# UV_BOX.net
KiCad netlist of a schematic drawn in EAGLE
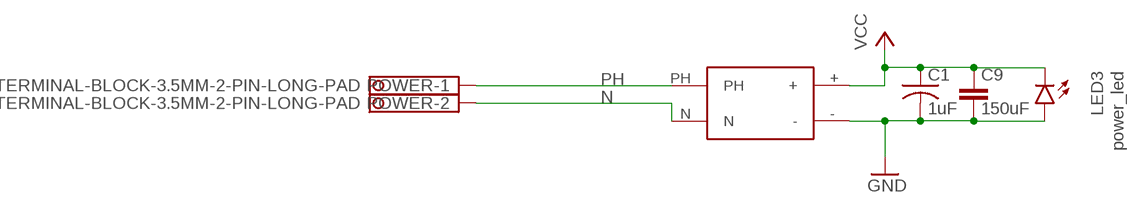
[diagram p0: schematic, sheet 1]
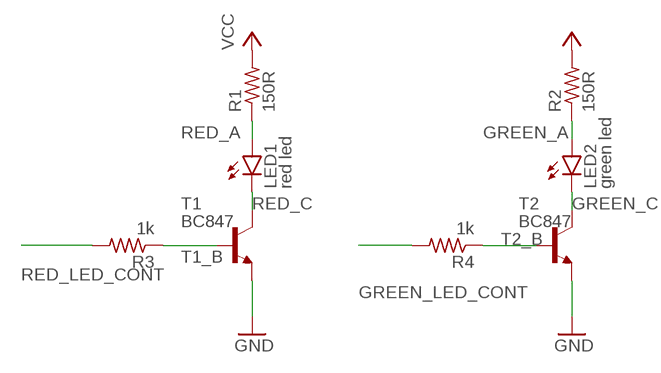
[diagram p1: schematic, sheet 2]
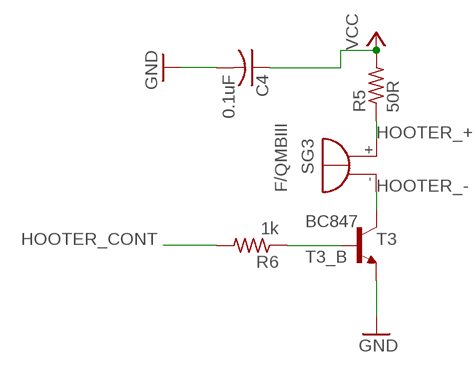
[diagram p2: schematic, sheet 3]
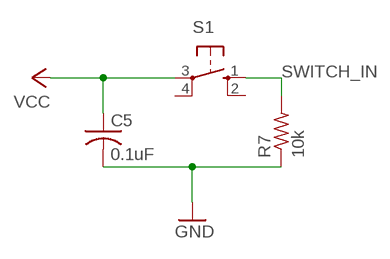
[diagram p3: schematic, sheet 4]
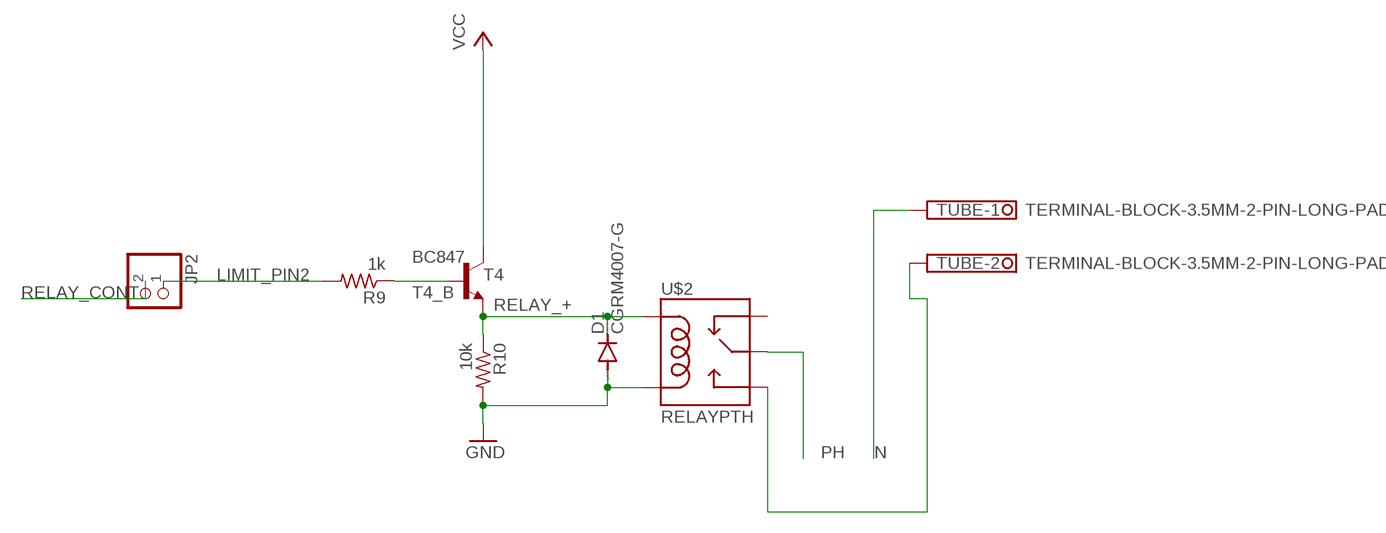
[diagram p4: schematic, sheet 5]
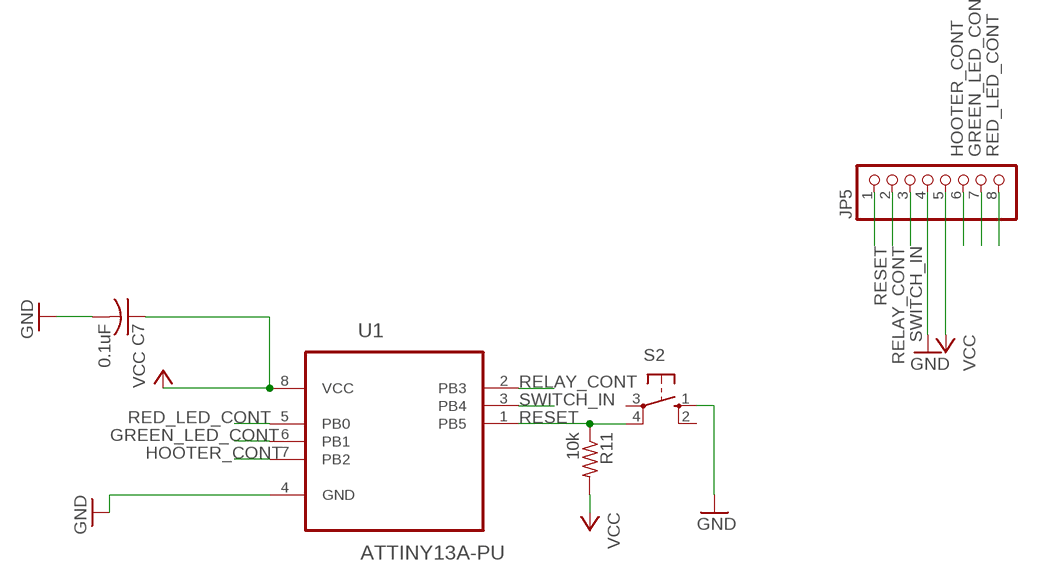
[diagram p5: schematic, sheet 6]

(export (version "E")
  (design (tool "Eeschema 10.0.6"))
  (components
    (comp (ref "D1")
      (value "CGRM4007-G")
      (footprint "eagle-import:SOD-123_MINI-SMA")
      (libsource (lib "eagle-import") (part "CGRM400-G7"))
    )
    (comp (ref "JP2")
      (value "PINHD-1X2")
      (footprint "eagle-import:1X02")
      (libsource (lib "eagle-import") (part "PINHD-1X2"))
    )
    (comp (ref "R9")
      (value "1k")
      (footprint "eagle-import:R1206")
      (libsource (lib "eagle-import") (part "R-US_R1206"))
    )
    (comp (ref "R10")
      (value "10k")
      (footprint "eagle-import:R1206")
      (libsource (lib "eagle-import") (part "R-US_R1206"))
    )
    (comp (ref "T4")
      (value "BC847")
      (footprint "eagle-import:SOT23")
      (libsource (lib "eagle-import") (part "BC847"))
    )
    (comp (ref "TUBE")
      (value "TERMINAL-BLOCK-3.5MM-2-PIN-LONG-PAD")
      (footprint "eagle-import:TERMINAL-BLOCK-2-PIN-3.5MM-LONG-PAD")
      (libsource (lib "eagle-import") (part "TERMINAL-BLOCK-3.5MM-2-PIN-LONG-PAD"))
    )
    (comp (ref "U$2")
      (value "RELAYPTH")
      (footprint "eagle-import:SRD-05VDC-SL-C")
      (libsource (lib "eagle-import") (part "RELAYPTH"))
    )
    (comp (ref "C7")
      (value "0.1uF")
      (footprint "eagle-import:C1206K")
      (libsource (lib "eagle-import") (part "C-USC1206K"))
    )
    (comp (ref "JP5")
      (value "PINHD-1X8")
      (footprint "eagle-import:1X08")
      (libsource (lib "eagle-import") (part "PINHD-1X8"))
    )
    (comp (ref "R11")
      (value "10k")
      (footprint "eagle-import:R1206")
      (libsource (lib "eagle-import") (part "R-US_R1206"))
    )
    (comp (ref "S2")
      (value "10-XX")
      (footprint "eagle-import:B3F-10XX")
      (fields (field (name "MPN") "B3F-1000"))
      (libsource (lib "eagle-import") (part "10-XX"))
    )
    (comp (ref "U1")
      (value "ATTINY13A-PU")
      (footprint "eagle-import:DIP254P762X533-8")
      (fields (field (name "MF") "Microchip"))
      (libsource (lib "eagle-import") (part "ATTINY13A-PU"))
    )
    (comp (ref "C1")
      (value "1uF")
      (footprint "eagle-import:C1206K")
      (libsource (lib "eagle-import") (part "C-USC1206K"))
    )
    (comp (ref "C9")
      (value "150uF")
      (footprint "eagle-import:C5B5")
      (libsource (lib "eagle-import") (part "C5/5"))
    )
    (comp (ref "LED3")
      (value "power_led")
      (footprint "eagle-import:CHIPLED_1206")
      (libsource (lib "eagle-import") (part "LEDCHIPLED_1206"))
    )
    (comp (ref "POWER")
      (value "TERMINAL-BLOCK-3.5MM-2-PIN-LONG-PAD")
      (footprint "eagle-import:TERMINAL-BLOCK-2-PIN-3.5MM-LONG-PAD")
      (libsource (lib "eagle-import") (part "TERMINAL-BLOCK-3.5MM-2-PIN-LONG-PAD"))
    )
    (comp (ref "U2")
      (value "AC/DCCONVERTER")
      (footprint "eagle-import:ACDC")
      (libsource (lib "eagle-import") (part "AC/DCCONVERTER"))
    )
    (comp (ref "C4")
      (value "0.1uF")
      (footprint "eagle-import:C1206K")
      (libsource (lib "eagle-import") (part "C-USC1206K"))
    )
    (comp (ref "R5")
      (value "50R")
      (footprint "eagle-import:R1206")
      (libsource (lib "eagle-import") (part "R-US_R1206"))
    )
    (comp (ref "R6")
      (value "1k")
      (footprint "eagle-import:R1206")
      (libsource (lib "eagle-import") (part "R-US_R1206"))
    )
    (comp (ref "SG3")
      (value "F/QMBIII")
      (footprint "eagle-import:F_QMBIII")
      (libsource (lib "eagle-import") (part "F/QMBIII"))
    )
    (comp (ref "T3")
      (value "BC847")
      (footprint "eagle-import:SOT23")
      (libsource (lib "eagle-import") (part "BC847"))
    )
    (comp (ref "LED1")
      (value "red led")
      (footprint "eagle-import:CHIPLED_1206")
      (libsource (lib "eagle-import") (part "LEDCHIPLED_1206"))
    )
    (comp (ref "LED2")
      (value "green led")
      (footprint "eagle-import:CHIPLED_1206")
      (libsource (lib "eagle-import") (part "LEDCHIPLED_1206"))
    )
    (comp (ref "R1")
      (value "150R")
      (footprint "eagle-import:R1206")
      (libsource (lib "eagle-import") (part "R-US_R1206"))
    )
    (comp (ref "R2")
      (value "150R")
      (footprint "eagle-import:R1206")
      (libsource (lib "eagle-import") (part "R-US_R1206"))
    )
    (comp (ref "R3")
      (value "1k")
      (footprint "eagle-import:R1206")
      (libsource (lib "eagle-import") (part "R-US_R1206"))
    )
    (comp (ref "R4")
      (value "1k")
      (footprint "eagle-import:R1206")
      (libsource (lib "eagle-import") (part "R-US_R1206"))
    )
    (comp (ref "T1")
      (value "BC847")
      (footprint "eagle-import:SOT23")
      (libsource (lib "eagle-import") (part "BC847"))
    )
    (comp (ref "T2")
      (value "BC847")
      (footprint "eagle-import:SOT23")
      (libsource (lib "eagle-import") (part "BC847"))
    )
    (comp (ref "C5")
      (value "0.1uF")
      (footprint "eagle-import:C1206K")
      (libsource (lib "eagle-import") (part "C-USC1206K"))
    )
    (comp (ref "R7")
      (value "10k")
      (footprint "eagle-import:R1206")
      (libsource (lib "eagle-import") (part "R-US_R1206"))
    )
    (comp (ref "S1")
      (value "40-XX")
      (footprint "eagle-import:B3F-40XX")
      (fields (field (name "MF") "OMRON COMPONENTS USA") (field (name "MPN") "B3F-4000"))
      (libsource (lib "eagle-import") (part "40-XX"))
    )
  )
  (nets
    (net (code "1") (name "GND") (class "Default")
      (node (ref "C1") (pin "2") (pinfunction "2_2") (pintype "passive"))
      (node (ref "C4") (pin "2") (pinfunction "2_2") (pintype "passive"))
      (node (ref "C5") (pin "2") (pinfunction "2_2") (pintype "passive"))
      (node (ref "C7") (pin "2") (pinfunction "2_2") (pintype "passive"))
      (node (ref "C9") (pin "2") (pinfunction "2_2") (pintype "passive"))
      (node (ref "D1") (pin "A") (pinfunction "A_A") (pintype "passive"))
      (node (ref "JP5") (pin "4") (pinfunction "4_4") (pintype "passive"))
      (node (ref "LED3") (pin "A") (pinfunction "A_A") (pintype "passive"))
      (node (ref "R10") (pin "2") (pinfunction "2_2") (pintype "passive"))
      (node (ref "R7") (pin "1") (pinfunction "1_1") (pintype "passive"))
      (node (ref "S2") (pin "1") (pinfunction "S_1") (pintype "passive"))
      (node (ref "T1") (pin "2") (pinfunction "E_2") (pintype "passive"))
      (node (ref "T2") (pin "2") (pinfunction "E_2") (pintype "passive"))
      (node (ref "T3") (pin "2") (pinfunction "E_2") (pintype "passive"))
      (node (ref "U$2") (pin "COIL0") (pinfunction "COIL0_COIL0") (pintype "bidirectional"))
      (node (ref "U1") (pin "4") (pinfunction "GND_4") (pintype "passive"))
      (node (ref "U2") (pin "-") (pinfunction "-_-") (pintype "bidirectional"))
    )
    (net (code "2") (name "GREEN_A") (class "Default")
      (node (ref "LED2") (pin "A") (pinfunction "A_A") (pintype "passive"))
      (node (ref "R2") (pin "1") (pinfunction "1_1") (pintype "passive"))
    )
    (net (code "3") (name "GREEN_C") (class "Default")
      (node (ref "LED2") (pin "C") (pinfunction "C_C") (pintype "passive"))
      (node (ref "T2") (pin "3") (pinfunction "C_3") (pintype "passive"))
    )
    (net (code "4") (name "GREEN_LED_CONT") (class "Default")
      (node (ref "JP5") (pin "7") (pinfunction "7_7") (pintype "passive"))
      (node (ref "R4") (pin "2") (pinfunction "2_2") (pintype "passive"))
      (node (ref "U1") (pin "6") (pinfunction "PB1_6") (pintype "bidirectional"))
    )
    (net (code "5") (name "HOOTER_+") (class "Default")
      (node (ref "R5") (pin "1") (pinfunction "1_1") (pintype "passive"))
      (node (ref "SG3") (pin "+") (pinfunction "-_+") (pintype "passive"))
    )
    (net (code "6") (name "HOOTER_-") (class "Default")
      (node (ref "SG3") (pin "-") (pinfunction "+_-") (pintype "passive"))
      (node (ref "T3") (pin "3") (pinfunction "C_3") (pintype "passive"))
    )
    (net (code "7") (name "HOOTER_CONT") (class "Default")
      (node (ref "JP5") (pin "6") (pinfunction "6_6") (pintype "passive"))
      (node (ref "R6") (pin "2") (pinfunction "2_2") (pintype "passive"))
      (node (ref "U1") (pin "7") (pinfunction "PB2_7") (pintype "bidirectional"))
    )
    (net (code "8") (name "LIMIT_PIN2") (class "Default")
      (node (ref "JP2") (pin "1") (pinfunction "1_1") (pintype "passive"))
      (node (ref "R9") (pin "2") (pinfunction "2_2") (pintype "passive"))
    )
    (net (code "9") (name "N") (class "Default")
      (node (ref "POWER") (pin "2") (pinfunction "K_2") (pintype "passive"))
      (node (ref "TUBE") (pin "1") (pinfunction "K_1") (pintype "passive"))
      (node (ref "U2") (pin "N") (pinfunction "N_N") (pintype "bidirectional"))
    )
    (net (code "10") (name "Net-(TUBEB-K)") (class "Default")
      (node (ref "TUBE") (pin "2") (pinfunction "K_2") (pintype "passive"))
      (node (ref "U$2") (pin "SWOPEN") (pinfunction "SWOPEN_SWOPEN") (pintype "bidirectional"))
    )
    (net (code "11") (name "PH") (class "Default")
      (node (ref "POWER") (pin "1") (pinfunction "K_1") (pintype "passive"))
      (node (ref "U$2") (pin "SWCOMMON") (pinfunction "SWCOMMON_SWCOMMON") (pintype "bidirectional"))
      (node (ref "U2") (pin "PH") (pinfunction "PH_PH") (pintype "bidirectional"))
    )
    (net (code "12") (name "RED_A") (class "Default")
      (node (ref "LED1") (pin "A") (pinfunction "A_A") (pintype "passive"))
      (node (ref "R1") (pin "1") (pinfunction "1_1") (pintype "passive"))
    )
    (net (code "13") (name "RED_C") (class "Default")
      (node (ref "LED1") (pin "C") (pinfunction "C_C") (pintype "passive"))
      (node (ref "T1") (pin "3") (pinfunction "C_3") (pintype "passive"))
    )
    (net (code "14") (name "RED_LED_CONT") (class "Default")
      (node (ref "JP5") (pin "8") (pinfunction "8_8") (pintype "passive"))
      (node (ref "R3") (pin "2") (pinfunction "2_2") (pintype "passive"))
      (node (ref "U1") (pin "5") (pinfunction "PB0_5") (pintype "bidirectional"))
    )
    (net (code "15") (name "RELAY_+") (class "Default")
      (node (ref "D1") (pin "C") (pinfunction "C_C") (pintype "passive"))
      (node (ref "R10") (pin "1") (pinfunction "1_1") (pintype "passive"))
      (node (ref "T4") (pin "2") (pinfunction "E_2") (pintype "passive"))
      (node (ref "U$2") (pin "COIL1") (pinfunction "COIL1_COIL1") (pintype "bidirectional"))
    )
    (net (code "16") (name "RELAY_CONT") (class "Default")
      (node (ref "JP2") (pin "2") (pinfunction "2_2") (pintype "passive"))
      (node (ref "JP5") (pin "2") (pinfunction "2_2") (pintype "passive"))
      (node (ref "U1") (pin "2") (pinfunction "PB3_2") (pintype "bidirectional"))
    )
    (net (code "17") (name "RESET") (class "Default")
      (node (ref "JP5") (pin "1") (pinfunction "1_1") (pintype "passive"))
      (node (ref "R11") (pin "1") (pinfunction "1_1") (pintype "passive"))
      (node (ref "S2") (pin "4") (pinfunction "P1_4") (pintype "passive"))
      (node (ref "U1") (pin "1") (pinfunction "PB5_1") (pintype "bidirectional"))
    )
    (net (code "18") (name "SWITCH_IN") (class "Default")
      (node (ref "JP5") (pin "3") (pinfunction "3_3") (pintype "passive"))
      (node (ref "R7") (pin "2") (pinfunction "2_2") (pintype "passive"))
      (node (ref "S1") (pin "1") (pinfunction "S_1") (pintype "passive"))
      (node (ref "U1") (pin "3") (pinfunction "PB4_3") (pintype "bidirectional"))
    )
    (net (code "19") (name "T1_B") (class "Default")
      (node (ref "R3") (pin "1") (pinfunction "1_1") (pintype "passive"))
      (node (ref "T1") (pin "1") (pinfunction "B_1") (pintype "passive"))
    )
    (net (code "20") (name "T2_B") (class "Default")
      (node (ref "R4") (pin "1") (pinfunction "1_1") (pintype "passive"))
      (node (ref "T2") (pin "1") (pinfunction "B_1") (pintype "passive"))
    )
    (net (code "21") (name "T3_B") (class "Default")
      (node (ref "R6") (pin "1") (pinfunction "1_1") (pintype "passive"))
      (node (ref "T3") (pin "1") (pinfunction "B_1") (pintype "passive"))
    )
    (net (code "22") (name "T4_B") (class "Default")
      (node (ref "R9") (pin "1") (pinfunction "1_1") (pintype "passive"))
      (node (ref "T4") (pin "1") (pinfunction "B_1") (pintype "passive"))
    )
    (net (code "23") (name "VCC") (class "Default")
      (node (ref "C1") (pin "1") (pinfunction "1_1") (pintype "passive"))
      (node (ref "C4") (pin "1") (pinfunction "1_1") (pintype "passive"))
      (node (ref "C5") (pin "1") (pinfunction "1_1") (pintype "passive"))
      (node (ref "C7") (pin "1") (pinfunction "1_1") (pintype "passive"))
      (node (ref "C9") (pin "1") (pinfunction "1_1") (pintype "passive"))
      (node (ref "JP5") (pin "5") (pinfunction "5_5") (pintype "passive"))
      (node (ref "LED3") (pin "C") (pinfunction "C_C") (pintype "passive"))
      (node (ref "R1") (pin "2") (pinfunction "2_2") (pintype "passive"))
      (node (ref "R11") (pin "2") (pinfunction "2_2") (pintype "passive"))
      (node (ref "R2") (pin "2") (pinfunction "2_2") (pintype "passive"))
      (node (ref "R5") (pin "2") (pinfunction "2_2") (pintype "passive"))
      (node (ref "S1") (pin "3") (pinfunction "P_3") (pintype "passive"))
      (node (ref "T4") (pin "3") (pinfunction "C_3") (pintype "passive"))
      (node (ref "U1") (pin "8") (pinfunction "VCC_8") (pintype "power_in"))
      (node (ref "U2") (pin "+") (pinfunction "+_+") (pintype "bidirectional"))
    )
    (net (code "24") (name "unconnected-(S1-P1-Pad4)") (class "Default")
      (node (ref "S1") (pin "4") (pinfunction "P1_4") (pintype "passive"))
    )
    (net (code "25") (name "unconnected-(S1-S1-Pad2)") (class "Default")
      (node (ref "S1") (pin "2") (pinfunction "S1_2") (pintype "passive"))
    )
    (net (code "26") (name "unconnected-(S2-P-Pad3)") (class "Default")
      (node (ref "S2") (pin "3") (pinfunction "P_3") (pintype "passive"))
    )
    (net (code "27") (name "unconnected-(S2-S1-Pad2)") (class "Default")
      (node (ref "S2") (pin "2") (pinfunction "S1_2") (pintype "passive"))
    )
    (net (code "28") (name "unconnected-(U$2-SWCLOSE-PadSWCLOSED)") (class "Default")
      (node (ref "U$2") (pin "SWCLOSED") (pinfunction "SWCLOSE_SWCLOSED") (pintype "bidirectional"))
    )
  )
)
